# 06_01_MCU.net
KiCad netlist of a schematic drawn in Altium Designer
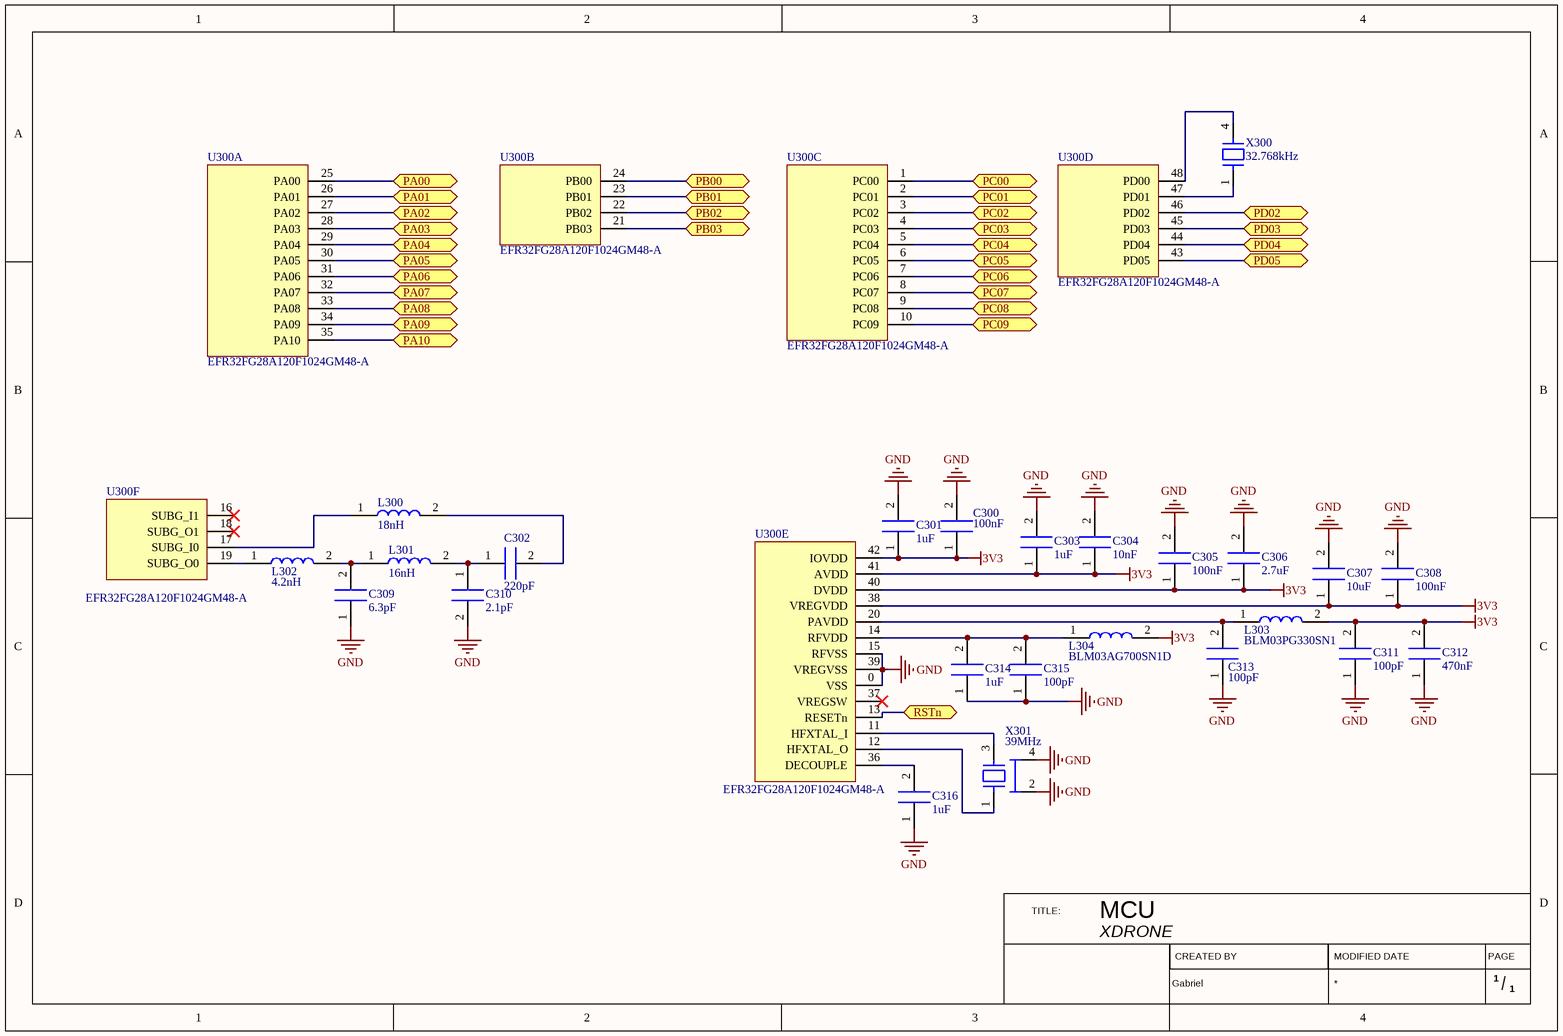
[diagram p0: 06_01_MCU.SchDoc]

(export (version "E")
  (design (tool "Eeschema 10.0.6"))
  (components
    (comp (ref "C300")
      (value "100nF")
      (footprint "CAP_0402")
      (description "CAPACITOR 100nF 10% X7R 0402")
      (fields (field (name "TOLERANCE") "10%") (field (name "MANUFACTURER") "MURATA"))
      (libsource (lib "Capacitors") (part "100nF_10%_16V_0402_GRM155R71C104KA88J"))
    )
    (comp (ref "C301")
      (value "1uF")
      (footprint "CAP_0402")
      (description "CAPACITOR 1uF 10% X5R 0402")
      (fields (field (name "TOLERANCE") "10%") (field (name "MANUFACTURER") "MURATA"))
      (libsource (lib "Capacitors") (part "1uF_10%_35V_0402_GRM155R6YA105KE11J"))
    )
    (comp (ref "C302")
      (value "220pF")
      (footprint "CAP_0805")
      (description "CAP 220pF 5% 50V 0805 C0G,NP0")
      (fields (field (name "TOLERANCE") "5%") (field (name "MANUFACTURER") "JOHANSON TECHLONOGY"))
      (libsource (lib "Capacitors") (part "220pF_5%_50V_0805_C0G,NP0_QSCT251Q221J1GV001E"))
    )
    (comp (ref "C303")
      (value "1uF")
      (footprint "CAP_0402")
      (description "CAPACITOR 1uF 10% X5R 0402")
      (fields (field (name "TOLERANCE") "10%") (field (name "MANUFACTURER") "MURATA"))
      (libsource (lib "Capacitors") (part "1uF_10%_35V_0402_GRM155R6YA105KE11J"))
    )
    (comp (ref "C304")
      (value "10nF")
      (footprint "CAP_0402")
      (description "CAPACITOR 10nF 10% 6.3V 0402 CC0402KRX7R5BB103")
      (fields (field (name "TOLERANCE") "10%") (field (name "MANUFACTURER") "YAGEO"))
      (libsource (lib "Capacitors") (part "10nF_10%_6.3V_0402_CC0402KRX7R5BB103"))
    )
    (comp (ref "C305")
      (value "100nF")
      (footprint "CAP_0402")
      (description "CAPACITOR 100nF 10% X7R 0402")
      (fields (field (name "TOLERANCE") "10%") (field (name "MANUFACTURER") "MURATA"))
      (libsource (lib "Capacitors") (part "100nF_10%_16V_0402_GRM155R71C104KA88J"))
    )
    (comp (ref "C306")
      (value "2.7uF")
      (footprint "CAP_0805")
      (description "CAP 2.7uF 10% 10V 0805 X5R C0805C275K8PAC7800")
      (fields (field (name "TOLERANCE") "10%") (field (name "MANUFACTURER") "KEMET"))
      (libsource (lib "Capacitors") (part "2.7uF_10%_10V_0805_X5R_C0805C275K8PAC7800"))
    )
    (comp (ref "C307")
      (value "10uF")
      (footprint "CAP_0402")
      (description "CAPACITOR 10uF 20% 6.3V 0402 GRM155R60J106ME05D")
      (fields (field (name "TOLERANCE") "20%") (field (name "MANUFACTURER") "MURATA"))
      (libsource (lib "Capacitors") (part "10uF 20% 6.3V 0402 GRM155R60J106ME05D"))
    )
    (comp (ref "C308")
      (value "100nF")
      (footprint "CAP_0402")
      (description "CAPACITOR 100nF 10% X7R 0402")
      (fields (field (name "TOLERANCE") "10%") (field (name "MANUFACTURER") "MURATA"))
      (libsource (lib "Capacitors") (part "100nF_10%_16V_0402_GRM155R71C104KA88J"))
    )
    (comp (ref "C309")
      (value "6.3pF")
      (footprint "CAP_0402")
      (description "CAPACITOR 6.3pF 1.5% 50V 0402 CBR04C639B5GAC")
      (fields (field (name "TOLERANCE") "1.5%") (field (name "MANUFACTURER") "KEMET"))
      (libsource (lib "Capacitors") (part "6.3pF_1.5%_50V_0402_CBR04C639B5GAC"))
    )
    (comp (ref "C310")
      (value "2.1pF")
      (footprint "CAP_0402")
      (description "CAPACITOR 2.1pF 5% 50V 0402 GJM1555C1H2R1BB01D")
      (fields (field (name "TOLERANCE") "5%") (field (name "MANUFACTURER") "MURATA"))
      (libsource (lib "Capacitors") (part "2.1pF_5%_50V_0402_GJM1555C1H2R1BB01D"))
    )
    (comp (ref "C311")
      (value "100pF")
      (footprint "CAP_0402")
      (description "CAPACITOR 100pF 5% 50V 0402 CC0402JRNPO9BN101")
      (fields (field (name "TOLERANCE") "5%") (field (name "MANUFACTURER") "YAGEO"))
      (libsource (lib "Capacitors") (part "100pF_5%_50V_0402_CC0402JRNPO9BN101"))
    )
    (comp (ref "C312")
      (value "470nF")
      (footprint "CAP_0402")
      (description "CAPACITOR 470nF 10% 6.3V 0402 GCM1555C1H101JA16D")
      (fields (field (name "TOLERANCE") "5%") (field (name "MANUFACTURER") "MURATA"))
      (libsource (lib "Capacitors") (part "470nF_10%_6.3V_0402_GCM1555C1H101JA16D"))
    )
    (comp (ref "C313")
      (value "100pF")
      (footprint "CAP_0402")
      (description "CAPACITOR 100pF 5% 50V 0402 CC0402JRNPO9BN101")
      (fields (field (name "TOLERANCE") "5%") (field (name "MANUFACTURER") "YAGEO"))
      (libsource (lib "Capacitors") (part "100pF_5%_50V_0402_CC0402JRNPO9BN101"))
    )
    (comp (ref "C314")
      (value "1uF")
      (footprint "CAP_0402")
      (description "CAPACITOR 1uF 10% X5R 0402")
      (fields (field (name "TOLERANCE") "10%") (field (name "MANUFACTURER") "MURATA"))
      (libsource (lib "Capacitors") (part "1uF_10%_35V_0402_GRM155R6YA105KE11J"))
    )
    (comp (ref "C315")
      (value "100pF")
      (footprint "CAP_0402")
      (description "CAPACITOR 100pF 5% 50V 0402 CC0402JRNPO9BN101")
      (fields (field (name "TOLERANCE") "5%") (field (name "MANUFACTURER") "YAGEO"))
      (libsource (lib "Capacitors") (part "100pF_5%_50V_0402_CC0402JRNPO9BN101"))
    )
    (comp (ref "C316")
      (value "1uF")
      (footprint "CAP_0402")
      (description "CAPACITOR 1uF 10% X5R 0402")
      (fields (field (name "TOLERANCE") "10%") (field (name "MANUFACTURER") "MURATA"))
      (libsource (lib "Capacitors") (part "1uF_10%_35V_0402_GRM155R6YA105KE11J"))
    )
    (comp (ref "L300")
      (value "18nH")
      (footprint "RF_IND_0402")
      (description "INDUCTOR 18nH 2% 400mA LQG15HS18NG02D")
      (fields (field (name "TOLERANCE") "2%") (field (name "MANUFACTURER") "MURATA"))
      (libsource (lib "Inductors") (part "18nH_2%_400mA_LQG15HS18NG02D"))
    )
    (comp (ref "L301")
      (value "16nH")
      (footprint "RF_IND_0402")
      (description "INDUCTOR 16nH 3% 400mA MLG1005S16NHT000")
      (fields (field (name "TOLERANCE") "3%") (field (name "MANUFACTURER") "TDK"))
      (libsource (lib "Inductors") (part "16nH_3%_400mA_MLG1005S16NHT000"))
    )
    (comp (ref "L302")
      (value "4.2nH")
      (footprint "RF_IND_0402")
      (description "INDUCTOR 4.2nH 5% 1.8A LQW15AN4N2C8ZD")
      (fields (field (name "TOLERANCE") "5%") (field (name "MANUFACTURER") "MURATA"))
      (libsource (lib "Inductors") (part "4.2nH_5%_1.8A_LQW15AN4N2C8ZD"))
    )
    (comp (ref "L303")
      (value "52nH_25%_750mA_BLM03PG330SN1")
      (footprint "IND_0201")
      (description "INDUCTOR 52uH 25% 750mA BLM03PG330SN1")
      (fields
        (field (name "TOLERANCE") "25%")
        (field (name "MANUFACTURER") "MURATA")
        (field (name "MANUFACTURER REFERENCE") "BLM03PG330SN1")
      )
      (libsource (lib "Inductors") (part "52nH_25%_750mA_BLM03PG330SN1"))
    )
    (comp (ref "L304")
      (value "110nH_50%_200mA_BLM03AG700SN1D")
      (footprint "IND_0201")
      (description "INDUCTOR 110nH 50% 200mA BLM03AG700SN1D")
      (fields
        (field (name "TOLERANCE") "50%")
        (field (name "MANUFACTURER") "MURATA")
        (field (name "MANUFACTURER REFERENCE") "BLM03AG700SN1D")
      )
      (libsource (lib "Inductors") (part "110nH 50% 200mA BLM03AG700SN1D"))
    )
    (comp (ref "U300")
      (value "MCU_1MB_256kB_EFR32FG28A120F1024GM48-A")
      (footprint "QFN48 0606")
      (description "MCU 1MB 256kB EFR32FG28A120F1024GM48-A")
      (fields
        (field (name "MANUFACTURER") "SILICON LABS")
        (field (name "MANUFACTURER REFERENCE") "EFR32FG28A120F1024GM48-A")
      )
      (libsource (lib "Semiconductor") (part "MCU_1MB_256kB_EFR32FG28A120F1024GM48-A"))
    )
    (comp (ref "X300")
      (value "QUARTZ_32.768kHz_20ppm_830016178")
      (footprint "QUARTZ_4-SOJ_5.5mm")
      (description "QUARTZ 32.768kHz 20ppm 830016178")
      (fields
        (field (name "MANUFACTURER") "WURTH")
        (field (name "TOLERANCE") "20 ppm")
        (field (name "FREQUENCY") "32.768kHz")
      )
      (libsource (lib "Oscillators") (part "QUARTZ_32.768kHz_20ppm_830016178"))
    )
    (comp (ref "X301")
      (value "QUARTZ_39MHz_10ppm_ECS-390-10-37B-CKM-TR")
      (footprint "QUARTZ_4-SMD")
      (description "QUARTZ 39MHz 10ppm ECS-390-10-37B-CKM-TR")
      (fields
        (field (name "MANUFACTURER") "ECS")
        (field (name "TOLERANCE") "10 ppm")
        (field (name "FREQUENCY") "39MHz")
      )
      (libsource (lib "Oscillators") (part "QUARTZ_39MHz_10ppm_ECS-390-10-37B-CKM-TR"))
    )
  )
  (nets
    (net (code "1") (name "/PA00") (class "Default")
      (node (ref "U300") (pin "25") (pinfunction "PA00_25") (pintype "passive"))
    )
    (net (code "2") (name "/PA01") (class "Default")
      (node (ref "U300") (pin "26") (pinfunction "PA01_26") (pintype "passive"))
    )
    (net (code "3") (name "/PA02") (class "Default")
      (node (ref "U300") (pin "27") (pinfunction "PA02_27") (pintype "passive"))
    )
    (net (code "4") (name "/PA03") (class "Default")
      (node (ref "U300") (pin "28") (pinfunction "PA03_28") (pintype "passive"))
    )
    (net (code "5") (name "/PA04") (class "Default")
      (node (ref "U300") (pin "29") (pinfunction "PA04_29") (pintype "passive"))
    )
    (net (code "6") (name "/PA05") (class "Default")
      (node (ref "U300") (pin "30") (pinfunction "PA05_30") (pintype "passive"))
    )
    (net (code "7") (name "/PA06") (class "Default")
      (node (ref "U300") (pin "31") (pinfunction "PA06_31") (pintype "passive"))
    )
    (net (code "8") (name "/PA07") (class "Default")
      (node (ref "U300") (pin "32") (pinfunction "PA07_32") (pintype "passive"))
    )
    (net (code "9") (name "/PA08") (class "Default")
      (node (ref "U300") (pin "33") (pinfunction "PA08_33") (pintype "passive"))
    )
    (net (code "10") (name "/PA09") (class "Default")
      (node (ref "U300") (pin "34") (pinfunction "PA09_34") (pintype "passive"))
    )
    (net (code "11") (name "/PA10") (class "Default")
      (node (ref "U300") (pin "35") (pinfunction "PA10_35") (pintype "passive"))
    )
    (net (code "12") (name "/PB00") (class "Default")
      (node (ref "U300") (pin "24") (pinfunction "PB00_24") (pintype "passive"))
    )
    (net (code "13") (name "/PB01") (class "Default")
      (node (ref "U300") (pin "23") (pinfunction "PB01_23") (pintype "passive"))
    )
    (net (code "14") (name "/PB02") (class "Default")
      (node (ref "U300") (pin "22") (pinfunction "PB02_22") (pintype "passive"))
    )
    (net (code "15") (name "/PB03") (class "Default")
      (node (ref "U300") (pin "21") (pinfunction "PB03_21") (pintype "passive"))
    )
    (net (code "16") (name "/PC00") (class "Default")
      (node (ref "U300") (pin "1") (pinfunction "PC00_1") (pintype "passive"))
    )
    (net (code "17") (name "/PC01") (class "Default")
      (node (ref "U300") (pin "2") (pinfunction "PC01_2") (pintype "passive"))
    )
    (net (code "18") (name "/PC02") (class "Default")
      (node (ref "U300") (pin "3") (pinfunction "PC02_3") (pintype "passive"))
    )
    (net (code "19") (name "/PC03") (class "Default")
      (node (ref "U300") (pin "4") (pinfunction "PC03_4") (pintype "passive"))
    )
    (net (code "20") (name "/PC04") (class "Default")
      (node (ref "U300") (pin "5") (pinfunction "PC04_5") (pintype "passive"))
    )
    (net (code "21") (name "/PC05") (class "Default")
      (node (ref "U300") (pin "6") (pinfunction "PC05_6") (pintype "passive"))
    )
    (net (code "22") (name "/PC06") (class "Default")
      (node (ref "U300") (pin "7") (pinfunction "PC06_7") (pintype "passive"))
    )
    (net (code "23") (name "/PC07") (class "Default")
      (node (ref "U300") (pin "8") (pinfunction "PC07_8") (pintype "passive"))
    )
    (net (code "24") (name "/PC08") (class "Default")
      (node (ref "U300") (pin "9") (pinfunction "PC08_9") (pintype "passive"))
    )
    (net (code "25") (name "/PC09") (class "Default")
      (node (ref "U300") (pin "10") (pinfunction "PC09_10") (pintype "passive"))
    )
    (net (code "26") (name "/PD02") (class "Default")
      (node (ref "U300") (pin "46") (pinfunction "PD02_46") (pintype "passive"))
    )
    (net (code "27") (name "/PD03") (class "Default")
      (node (ref "U300") (pin "45") (pinfunction "PD03_45") (pintype "passive"))
    )
    (net (code "28") (name "/PD04") (class "Default")
      (node (ref "U300") (pin "44") (pinfunction "PD04_44") (pintype "passive"))
    )
    (net (code "29") (name "/PD05") (class "Default")
      (node (ref "U300") (pin "43") (pinfunction "PD05_43") (pintype "passive"))
    )
    (net (code "30") (name "/RSTn") (class "Default")
      (node (ref "U300") (pin "13") (pinfunction "RESETn_13") (pintype "passive"))
    )
    (net (code "31") (name "3V3") (class "Default")
      (node (ref "C300") (pin "1") (pinfunction "1_1") (pintype "passive"))
      (node (ref "C301") (pin "1") (pinfunction "1_1") (pintype "passive"))
      (node (ref "C303") (pin "1") (pinfunction "1_1") (pintype "passive"))
      (node (ref "C304") (pin "1") (pinfunction "1_1") (pintype "passive"))
      (node (ref "C305") (pin "1") (pinfunction "1_1") (pintype "passive"))
      (node (ref "C306") (pin "1") (pinfunction "1_1") (pintype "passive"))
      (node (ref "C307") (pin "1") (pinfunction "1_1") (pintype "passive"))
      (node (ref "C308") (pin "1") (pinfunction "1_1") (pintype "passive"))
      (node (ref "C311") (pin "2") (pinfunction "2_2") (pintype "passive"))
      (node (ref "C312") (pin "2") (pinfunction "2_2") (pintype "passive"))
      (node (ref "L303") (pin "2") (pinfunction "2_2") (pintype "passive"))
      (node (ref "L304") (pin "2") (pinfunction "2_2") (pintype "passive"))
      (node (ref "U300") (pin "38") (pinfunction "VREGVDD_38") (pintype "passive"))
      (node (ref "U300") (pin "40") (pinfunction "DVDD_40") (pintype "passive"))
      (node (ref "U300") (pin "41") (pinfunction "AVDD_41") (pintype "passive"))
      (node (ref "U300") (pin "42") (pinfunction "IOVDD_42") (pintype "passive"))
    )
    (net (code "32") (name "GND") (class "Default")
      (node (ref "C300") (pin "2") (pinfunction "2_2") (pintype "passive"))
      (node (ref "C301") (pin "2") (pinfunction "2_2") (pintype "passive"))
      (node (ref "C303") (pin "2") (pinfunction "2_2") (pintype "passive"))
      (node (ref "C304") (pin "2") (pinfunction "2_2") (pintype "passive"))
      (node (ref "C305") (pin "2") (pinfunction "2_2") (pintype "passive"))
      (node (ref "C306") (pin "2") (pinfunction "2_2") (pintype "passive"))
      (node (ref "C307") (pin "2") (pinfunction "2_2") (pintype "passive"))
      (node (ref "C308") (pin "2") (pinfunction "2_2") (pintype "passive"))
      (node (ref "C309") (pin "1") (pinfunction "1_1") (pintype "passive"))
      (node (ref "C310") (pin "2") (pinfunction "2_2") (pintype "passive"))
      (node (ref "C311") (pin "1") (pinfunction "1_1") (pintype "passive"))
      (node (ref "C312") (pin "1") (pinfunction "1_1") (pintype "passive"))
      (node (ref "C313") (pin "1") (pinfunction "1_1") (pintype "passive"))
      (node (ref "C314") (pin "1") (pinfunction "1_1") (pintype "passive"))
      (node (ref "C315") (pin "1") (pinfunction "1_1") (pintype "passive"))
      (node (ref "C316") (pin "1") (pinfunction "1_1") (pintype "passive"))
      (node (ref "U300") (pin "0") (pinfunction "VSS_0") (pintype "passive"))
      (node (ref "U300") (pin "15") (pinfunction "RFVSS_15") (pintype "passive"))
      (node (ref "U300") (pin "39") (pinfunction "VREGVSS_39") (pintype "passive"))
      (node (ref "X301") (pin "2") (pinfunction "2_2") (pintype "passive"))
      (node (ref "X301") (pin "4") (pinfunction "4_4") (pintype "passive"))
    )
    (net (code "33") (name "Net-(C302-Pad1)") (class "Default")
      (node (ref "C302") (pin "1") (pinfunction "1_1") (pintype "passive"))
      (node (ref "C310") (pin "1") (pinfunction "1_1") (pintype "passive"))
      (node (ref "L301") (pin "2") (pinfunction "2_2") (pintype "passive"))
    )
    (net (code "34") (name "Net-(C302-Pad2)") (class "Default")
      (node (ref "C302") (pin "2") (pinfunction "2_2") (pintype "passive"))
      (node (ref "L300") (pin "2") (pinfunction "2_2") (pintype "passive"))
    )
    (net (code "35") (name "Net-(C309-Pad2)") (class "Default")
      (node (ref "C309") (pin "2") (pinfunction "2_2") (pintype "passive"))
      (node (ref "L301") (pin "1") (pinfunction "1_1") (pintype "passive"))
      (node (ref "L302") (pin "2") (pinfunction "2_2") (pintype "passive"))
    )
    (net (code "36") (name "Net-(U300D-PD00)") (class "Default")
      (node (ref "U300") (pin "48") (pinfunction "PD00_48") (pintype "passive"))
      (node (ref "X300") (pin "4") (pinfunction "4_4") (pintype "passive"))
    )
    (net (code "37") (name "Net-(U300D-PD01)") (class "Default")
      (node (ref "U300") (pin "47") (pinfunction "PD01_47") (pintype "passive"))
      (node (ref "X300") (pin "1") (pinfunction "1_1") (pintype "passive"))
    )
    (net (code "38") (name "Net-(U300E-DECOUPLE)") (class "Default")
      (node (ref "C316") (pin "2") (pinfunction "2_2") (pintype "passive"))
      (node (ref "U300") (pin "36") (pinfunction "DECOUPLE_36") (pintype "passive"))
    )
    (net (code "39") (name "Net-(U300E-HFXTAL_I)") (class "Default")
      (node (ref "U300") (pin "11") (pinfunction "HFXTAL_I_11") (pintype "passive"))
      (node (ref "X301") (pin "3") (pinfunction "3_3") (pintype "passive"))
    )
    (net (code "40") (name "Net-(U300E-HFXTAL_O)") (class "Default")
      (node (ref "U300") (pin "12") (pinfunction "HFXTAL_O_12") (pintype "passive"))
      (node (ref "X301") (pin "1") (pinfunction "1_1") (pintype "passive"))
    )
    (net (code "41") (name "Net-(U300E-PAVDD)") (class "Default")
      (node (ref "C313") (pin "2") (pinfunction "2_2") (pintype "passive"))
      (node (ref "L303") (pin "1") (pinfunction "1_1") (pintype "passive"))
      (node (ref "U300") (pin "20") (pinfunction "PAVDD_20") (pintype "passive"))
    )
    (net (code "42") (name "Net-(U300E-RFVDD)") (class "Default")
      (node (ref "C314") (pin "2") (pinfunction "2_2") (pintype "passive"))
      (node (ref "C315") (pin "2") (pinfunction "2_2") (pintype "passive"))
      (node (ref "L304") (pin "1") (pinfunction "1_1") (pintype "passive"))
      (node (ref "U300") (pin "14") (pinfunction "RFVDD_14") (pintype "passive"))
    )
    (net (code "43") (name "Net-(U300F-SUBG_I0)") (class "Default")
      (node (ref "L300") (pin "1") (pinfunction "1_1") (pintype "passive"))
      (node (ref "U300") (pin "17") (pinfunction "SUBG_I0_17") (pintype "passive"))
    )
    (net (code "44") (name "Net-(U300F-SUBG_O0)") (class "Default")
      (node (ref "L302") (pin "1") (pinfunction "1_1") (pintype "passive"))
      (node (ref "U300") (pin "19") (pinfunction "SUBG_O0_19") (pintype "passive"))
    )
    (net (code "45") (name "unconnected-(U300E-VREGSW-Pad37)") (class "Default")
      (node (ref "U300") (pin "37") (pinfunction "VREGSW_37") (pintype "passive+no_connect"))
    )
    (net (code "46") (name "unconnected-(U300F-SUBG_I1-Pad16)") (class "Default")
      (node (ref "U300") (pin "16") (pinfunction "SUBG_I1_16") (pintype "passive+no_connect"))
    )
    (net (code "47") (name "unconnected-(U300F-SUBG_O1-Pad18)") (class "Default")
      (node (ref "U300") (pin "18") (pinfunction "SUBG_O1_18") (pintype "passive+no_connect"))
    )
  )
)
